# Sheet1.net
KiCad netlist of a schematic drawn in Altium Designer
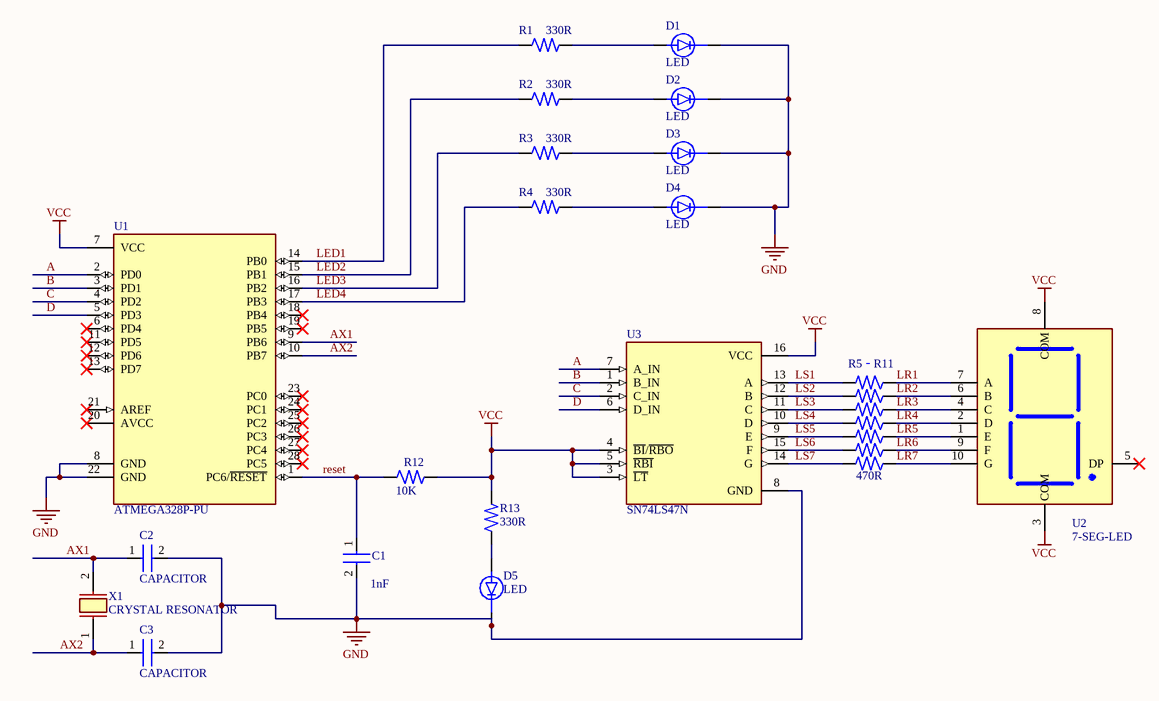
[diagram p0: Sheet1.SchDoc]

(export (version "E")
  (design (tool "Eeschema 10.0.6"))
  (components
    (comp (ref "C1") (value "1nF") (footprint "CAP_8x11mm") (libsource (lib "Schlib1") (part "CAPACITOR")))
    (comp (ref "C2")
      (value "CAPACITOR")
      (footprint "CAP_8x11mm")
      (libsource (lib "Schlib1") (part "CAPACITOR"))
    )
    (comp (ref "C3")
      (value "CAPACITOR")
      (footprint "CAP_8x11mm")
      (libsource (lib "Schlib1") (part "CAPACITOR"))
    )
    (comp (ref "D1") (value "LED") (footprint "LED-TH-2.54mm-RED") (libsource (lib "Schlib1") (part "LED")))
    (comp (ref "D2") (value "LED") (footprint "LED-TH-2.54mm-RED") (libsource (lib "Schlib1") (part "LED")))
    (comp (ref "D3") (value "LED") (footprint "LED-TH-2.54mm-RED") (libsource (lib "Schlib1") (part "LED")))
    (comp (ref "D4") (value "LED") (footprint "LED-TH-2.54mm-RED") (libsource (lib "Schlib1") (part "LED")))
    (comp (ref "D5") (value "LED") (footprint "LED-TH-2.54mm-RED") (libsource (lib "Schlib1") (part "LED")))
    (comp (ref "R1")
      (value "330R")
      (footprint "RES0805_SMD")
      (description "Resistor Symbol")
      (libsource (lib "Schlib1") (part "RESISTOR"))
    )
    (comp (ref "R2")
      (value "330R")
      (footprint "RES0805_SMD")
      (description "Resistor Symbol")
      (libsource (lib "Schlib1") (part "RESISTOR"))
    )
    (comp (ref "R3")
      (value "330R")
      (footprint "RES0805_SMD")
      (description "Resistor Symbol")
      (libsource (lib "Schlib1") (part "RESISTOR"))
    )
    (comp (ref "R4")
      (value "330R")
      (footprint "RES0805_SMD")
      (description "Resistor Symbol")
      (libsource (lib "Schlib1") (part "RESISTOR"))
    )
    (comp (ref "R5")
      (value "470R")
      (footprint "RES0805_SMD")
      (description "Resistor Symbol")
      (libsource (lib "Schlib1") (part "RESISTOR"))
    )
    (comp (ref "R6")
      (value "470R")
      (footprint "RES0805_SMD")
      (description "Resistor Symbol")
      (libsource (lib "Schlib1") (part "RESISTOR"))
    )
    (comp (ref "R7")
      (value "470R")
      (footprint "RES0805_SMD")
      (description "Resistor Symbol")
      (libsource (lib "Schlib1") (part "RESISTOR"))
    )
    (comp (ref "R8")
      (value "470R")
      (footprint "RES0805_SMD")
      (description "Resistor Symbol")
      (libsource (lib "Schlib1") (part "RESISTOR"))
    )
    (comp (ref "R9")
      (value "470R")
      (footprint "RES0805_SMD")
      (description "Resistor Symbol")
      (libsource (lib "Schlib1") (part "RESISTOR"))
    )
    (comp (ref "R10")
      (value "470R")
      (footprint "RES0805_SMD")
      (description "Resistor Symbol")
      (libsource (lib "Schlib1") (part "RESISTOR"))
    )
    (comp (ref "R11")
      (value "470R")
      (footprint "RES0805_SMD")
      (description "Resistor Symbol")
      (libsource (lib "Schlib1") (part "RESISTOR"))
    )
    (comp (ref "R12")
      (value "10K")
      (footprint "RES0805_SMD")
      (description "Resistor Symbol")
      (libsource (lib "Schlib1") (part "RESISTOR"))
    )
    (comp (ref "R13")
      (value "330R")
      (footprint "RES0805_SMD")
      (description "Resistor Symbol")
      (libsource (lib "Schlib1") (part "RESISTOR"))
    )
    (comp (ref "U1")
      (value "ATMEGA328P-PU")
      (footprint "DIP794W46P254L2967H457Q28B")
      (description "ATmega Series 20 MHz 32 KB Flash 2 KB SRAM 8-Bit Microcontroller - DIP-28")
      (libsource (lib "Schlib1") (part "ATMEGA328P-PU"))
    )
    (comp (ref "U2")
      (value "7-SEG-LED")
      (footprint "LED_INND-TS56YGAB")
      (fields (field (name "MF") "{'manufacturer': u'Inolux'}") (field (name "MP") "INND-TS56YGAB"))
      (libsource (lib "Schlib1") (part "7-SEG-LED"))
    )
    (comp (ref "U3")
      (value "SN74LS47N")
      (footprint "DIP794W45P254L1930H508Q16")
      (description "BCD-to-Seven-Segment Decoders/Drivers")
      (fields (field (name "MF") "Texas Instruments"))
      (libsource (lib "Schlib1") (part "SN74LS47N"))
    )
    (comp (ref "X1")
      (value "CRYSTAL RESONATOR")
      (footprint "XTAL_HC49P488W43L1150T466H350")
      (libsource (lib "Schlib1") (part "CRYSTAL RESONATOR"))
    )
  )
  (nets
    (net (code "1") (name "/A") (class "Default")
      (node (ref "U1") (pin "2") (pinfunction "PD0_2") (pintype "bidirectional"))
      (node (ref "U3") (pin "7") (pinfunction "A_IN_7") (pintype "input"))
    )
    (net (code "2") (name "/AX1") (class "Default")
      (node (ref "C2") (pin "1") (pinfunction "1_1") (pintype "passive"))
      (node (ref "U1") (pin "9") (pinfunction "PB6_9") (pintype "bidirectional"))
      (node (ref "X1") (pin "2") (pinfunction "2_2") (pintype "passive"))
    )
    (net (code "3") (name "/AX2") (class "Default")
      (node (ref "C3") (pin "1") (pinfunction "1_1") (pintype "passive"))
      (node (ref "U1") (pin "10") (pinfunction "PB7_10") (pintype "bidirectional"))
      (node (ref "X1") (pin "1") (pinfunction "1_1") (pintype "passive"))
    )
    (net (code "4") (name "/B") (class "Default")
      (node (ref "U1") (pin "3") (pinfunction "PD1_3") (pintype "bidirectional"))
      (node (ref "U3") (pin "1") (pinfunction "B_IN_1") (pintype "input"))
    )
    (net (code "5") (name "/C") (class "Default")
      (node (ref "U1") (pin "4") (pinfunction "PD2_4") (pintype "bidirectional"))
      (node (ref "U3") (pin "2") (pinfunction "C_IN_2") (pintype "input"))
    )
    (net (code "6") (name "/D") (class "Default")
      (node (ref "U1") (pin "5") (pinfunction "PD3_5") (pintype "bidirectional"))
      (node (ref "U3") (pin "6") (pinfunction "D_IN_6") (pintype "input"))
    )
    (net (code "7") (name "/LED1") (class "Default")
      (node (ref "R1") (pin "1") (pinfunction "1_1") (pintype "passive"))
      (node (ref "U1") (pin "14") (pinfunction "PB0_14") (pintype "bidirectional"))
    )
    (net (code "8") (name "/LED2") (class "Default")
      (node (ref "R2") (pin "1") (pinfunction "1_1") (pintype "passive"))
      (node (ref "U1") (pin "15") (pinfunction "PB1_15") (pintype "bidirectional"))
    )
    (net (code "9") (name "/LED3") (class "Default")
      (node (ref "R3") (pin "1") (pinfunction "1_1") (pintype "passive"))
      (node (ref "U1") (pin "16") (pinfunction "PB2_16") (pintype "bidirectional"))
    )
    (net (code "10") (name "/LED4") (class "Default")
      (node (ref "R4") (pin "1") (pinfunction "1_1") (pintype "passive"))
      (node (ref "U1") (pin "17") (pinfunction "PB3_17") (pintype "bidirectional"))
    )
    (net (code "11") (name "/LR1") (class "Default")
      (node (ref "R5") (pin "1") (pinfunction "1_1") (pintype "passive"))
      (node (ref "U2") (pin "7") (pinfunction "A_7") (pintype "passive"))
    )
    (net (code "12") (name "/LR2") (class "Default")
      (node (ref "R6") (pin "1") (pinfunction "1_1") (pintype "passive"))
      (node (ref "U2") (pin "6") (pinfunction "B_6") (pintype "passive"))
    )
    (net (code "13") (name "/LR3") (class "Default")
      (node (ref "R7") (pin "1") (pinfunction "1_1") (pintype "passive"))
      (node (ref "U2") (pin "4") (pinfunction "C_4") (pintype "passive"))
    )
    (net (code "14") (name "/LR4") (class "Default")
      (node (ref "R8") (pin "1") (pinfunction "1_1") (pintype "passive"))
      (node (ref "U2") (pin "2") (pinfunction "D_2") (pintype "passive"))
    )
    (net (code "15") (name "/LR5") (class "Default")
      (node (ref "R9") (pin "1") (pinfunction "1_1") (pintype "passive"))
      (node (ref "U2") (pin "1") (pinfunction "E_1") (pintype "passive"))
    )
    (net (code "16") (name "/LR6") (class "Default")
      (node (ref "R10") (pin "1") (pinfunction "1_1") (pintype "passive"))
      (node (ref "U2") (pin "9") (pinfunction "F_9") (pintype "passive"))
    )
    (net (code "17") (name "/LR7") (class "Default")
      (node (ref "R11") (pin "1") (pinfunction "1_1") (pintype "passive"))
      (node (ref "U2") (pin "10") (pinfunction "G_10") (pintype "passive"))
    )
    (net (code "18") (name "/LS1") (class "Default")
      (node (ref "R5") (pin "2") (pinfunction "2_2") (pintype "passive"))
      (node (ref "U3") (pin "13") (pinfunction "A_13") (pintype "output"))
    )
    (net (code "19") (name "/LS2") (class "Default")
      (node (ref "R6") (pin "2") (pinfunction "2_2") (pintype "passive"))
      (node (ref "U3") (pin "12") (pinfunction "B_12") (pintype "output"))
    )
    (net (code "20") (name "/LS3") (class "Default")
      (node (ref "R7") (pin "2") (pinfunction "2_2") (pintype "passive"))
      (node (ref "U3") (pin "11") (pinfunction "C_11") (pintype "output"))
    )
    (net (code "21") (name "/LS4") (class "Default")
      (node (ref "R8") (pin "2") (pinfunction "2_2") (pintype "passive"))
      (node (ref "U3") (pin "10") (pinfunction "D_10") (pintype "output"))
    )
    (net (code "22") (name "/LS5") (class "Default")
      (node (ref "R9") (pin "2") (pinfunction "2_2") (pintype "passive"))
      (node (ref "U3") (pin "9") (pinfunction "E_9") (pintype "output"))
    )
    (net (code "23") (name "/LS6") (class "Default")
      (node (ref "R10") (pin "2") (pinfunction "2_2") (pintype "passive"))
      (node (ref "U3") (pin "15") (pinfunction "F_15") (pintype "output"))
    )
    (net (code "24") (name "/LS7") (class "Default")
      (node (ref "R11") (pin "2") (pinfunction "2_2") (pintype "passive"))
      (node (ref "U3") (pin "14") (pinfunction "G_14") (pintype "output"))
    )
    (net (code "25") (name "/reset") (class "Default")
      (node (ref "C1") (pin "1") (pinfunction "1_1") (pintype "passive"))
      (node (ref "R12") (pin "1") (pinfunction "1_1") (pintype "passive"))
      (node (ref "U1") (pin "1") (pinfunction "PC6/~{RESET}_1") (pintype "bidirectional"))
    )
    (net (code "26") (name "GND") (class "Default")
      (node (ref "C1") (pin "2") (pinfunction "2_2") (pintype "passive"))
      (node (ref "C2") (pin "2") (pinfunction "2_2") (pintype "passive"))
      (node (ref "C3") (pin "2") (pinfunction "2_2") (pintype "passive"))
      (node (ref "D1") (pin "2") (pinfunction "K_2") (pintype "passive"))
      (node (ref "D2") (pin "2") (pinfunction "K_2") (pintype "passive"))
      (node (ref "D3") (pin "2") (pinfunction "K_2") (pintype "passive"))
      (node (ref "D4") (pin "2") (pinfunction "K_2") (pintype "passive"))
      (node (ref "D5") (pin "2") (pinfunction "K_2") (pintype "passive"))
      (node (ref "U1") (pin "22") (pinfunction "GND_22") (pintype "power_in"))
      (node (ref "U1") (pin "8") (pinfunction "GND_8") (pintype "power_in"))
      (node (ref "U3") (pin "8") (pinfunction "GND_8") (pintype "power_in"))
    )
    (net (code "27") (name "Net-(D1-A)") (class "Default")
      (node (ref "D1") (pin "1") (pinfunction "A_1") (pintype "passive"))
      (node (ref "R1") (pin "2") (pinfunction "2_2") (pintype "passive"))
    )
    (net (code "28") (name "Net-(D2-A)") (class "Default")
      (node (ref "D2") (pin "1") (pinfunction "A_1") (pintype "passive"))
      (node (ref "R2") (pin "2") (pinfunction "2_2") (pintype "passive"))
    )
    (net (code "29") (name "Net-(D3-A)") (class "Default")
      (node (ref "D3") (pin "1") (pinfunction "A_1") (pintype "passive"))
      (node (ref "R3") (pin "2") (pinfunction "2_2") (pintype "passive"))
    )
    (net (code "30") (name "Net-(D4-A)") (class "Default")
      (node (ref "D4") (pin "1") (pinfunction "A_1") (pintype "passive"))
      (node (ref "R4") (pin "2") (pinfunction "2_2") (pintype "passive"))
    )
    (net (code "31") (name "Net-(D5-A)") (class "Default")
      (node (ref "D5") (pin "1") (pinfunction "A_1") (pintype "passive"))
      (node (ref "R13") (pin "1") (pinfunction "1_1") (pintype "passive"))
    )
    (net (code "32") (name "VCC") (class "Default")
      (node (ref "R12") (pin "2") (pinfunction "2_2") (pintype "passive"))
      (node (ref "R13") (pin "2") (pinfunction "2_2") (pintype "passive"))
      (node (ref "U1") (pin "7") (pinfunction "VCC_7") (pintype "power_in"))
      (node (ref "U2") (pin "3") (pinfunction "COM_3") (pintype "passive"))
      (node (ref "U2") (pin "8") (pinfunction "COM_8") (pintype "passive"))
      (node (ref "U3") (pin "16") (pinfunction "VCC_16") (pintype "power_in"))
      (node (ref "U3") (pin "3") (pinfunction "~{LT}_3") (pintype "input"))
      (node (ref "U3") (pin "4") (pinfunction "~{BI}/~{RBO}_4") (pintype "input"))
      (node (ref "U3") (pin "5") (pinfunction "~{RBI}_5") (pintype "input"))
    )
    (net (code "33") (name "unconnected-(U1-AREF-Pad21)") (class "Default")
      (node (ref "U1") (pin "21") (pinfunction "AREF_21") (pintype "input+no_connect"))
    )
    (net (code "34") (name "unconnected-(U1-AVCC-Pad20)") (class "Default")
      (node (ref "U1") (pin "20") (pinfunction "AVCC_20") (pintype "power_in+no_connect"))
    )
    (net (code "35") (name "unconnected-(U1-PB4-Pad18)") (class "Default")
      (node (ref "U1") (pin "18") (pinfunction "PB4_18") (pintype "bidirectional+no_connect"))
    )
    (net (code "36") (name "unconnected-(U1-PB5-Pad19)") (class "Default")
      (node (ref "U1") (pin "19") (pinfunction "PB5_19") (pintype "bidirectional+no_connect"))
    )
    (net (code "37") (name "unconnected-(U1-PC0-Pad23)") (class "Default")
      (node (ref "U1") (pin "23") (pinfunction "PC0_23") (pintype "bidirectional+no_connect"))
    )
    (net (code "38") (name "unconnected-(U1-PC1-Pad24)") (class "Default")
      (node (ref "U1") (pin "24") (pinfunction "PC1_24") (pintype "bidirectional+no_connect"))
    )
    (net (code "39") (name "unconnected-(U1-PC2-Pad25)") (class "Default")
      (node (ref "U1") (pin "25") (pinfunction "PC2_25") (pintype "bidirectional+no_connect"))
    )
    (net (code "40") (name "unconnected-(U1-PC3-Pad26)") (class "Default")
      (node (ref "U1") (pin "26") (pinfunction "PC3_26") (pintype "bidirectional+no_connect"))
    )
    (net (code "41") (name "unconnected-(U1-PC4-Pad27)") (class "Default")
      (node (ref "U1") (pin "27") (pinfunction "PC4_27") (pintype "bidirectional+no_connect"))
    )
    (net (code "42") (name "unconnected-(U1-PC5-Pad28)") (class "Default")
      (node (ref "U1") (pin "28") (pinfunction "PC5_28") (pintype "bidirectional+no_connect"))
    )
    (net (code "43") (name "unconnected-(U1-PD4-Pad6)") (class "Default")
      (node (ref "U1") (pin "6") (pinfunction "PD4_6") (pintype "bidirectional+no_connect"))
    )
    (net (code "44") (name "unconnected-(U1-PD5-Pad11)") (class "Default")
      (node (ref "U1") (pin "11") (pinfunction "PD5_11") (pintype "bidirectional+no_connect"))
    )
    (net (code "45") (name "unconnected-(U1-PD6-Pad12)") (class "Default")
      (node (ref "U1") (pin "12") (pinfunction "PD6_12") (pintype "bidirectional+no_connect"))
    )
    (net (code "46") (name "unconnected-(U1-PD7-Pad13)") (class "Default")
      (node (ref "U1") (pin "13") (pinfunction "PD7_13") (pintype "bidirectional+no_connect"))
    )
    (net (code "47") (name "unconnected-(U2-DP-Pad5)") (class "Default")
      (node (ref "U2") (pin "5") (pinfunction "DP_5") (pintype "passive+no_connect"))
    )
  )
)
